# WiFiKernel.net
KiCad netlist of a schematic drawn in Altium Designer
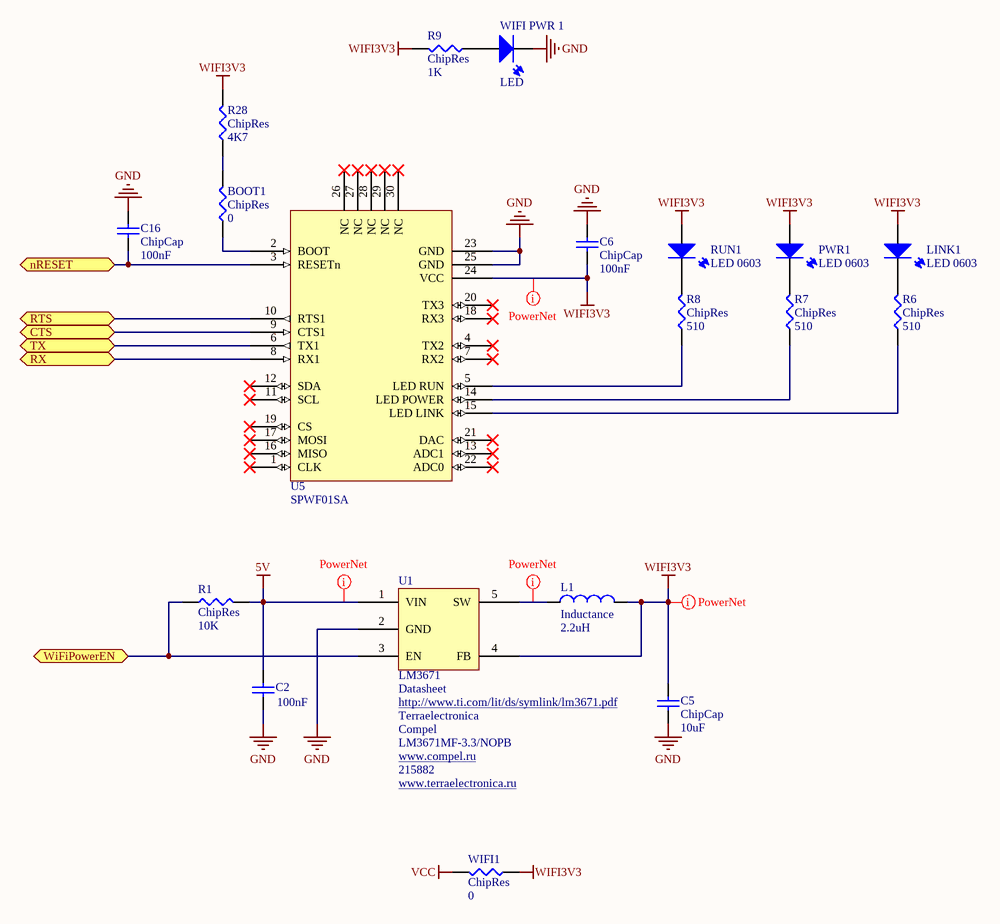
[diagram p0: WiFiKernel.SchDoc]

(export (version "E")
  (design (tool "Eeschema 10.0.6"))
  (components
    (comp (ref "BOOT1")
      (value "ChipRes")
      (footprint "RES0805")
      (description "Chip resistor")
      (fields (field (name "ALTIUM_VALUE") "0"))
      (libsource (lib "Common Devices") (part "ChipRes"))
    )
    (comp (ref "C2")
      (value "100nF")
      (footprint "CAP1210")
      (description "Capacitor")
      (fields (field (name "Comment") "ChipCap") (field (name "PUBLISHER") "Altium Limited"))
      (libsource (lib "Common Devices") (part "ChipCap"))
    )
    (comp (ref "C5")
      (value "ChipCap")
      (footprint "CAP1210")
      (description "Capacitor")
      (fields (field (name "ALTIUM_VALUE") "10uF") (field (name "PUBLISHER") "Altium Limited"))
      (libsource (lib "Common Devices") (part "ChipCap"))
    )
    (comp (ref "C6")
      (value "ChipCap")
      (footprint "CAP0805")
      (description "Capacitor")
      (fields (field (name "ALTIUM_VALUE") "100nF") (field (name "PUBLISHER") "Altium Limited"))
      (libsource (lib "Common Devices") (part "ChipCap"))
    )
    (comp (ref "C16")
      (value "ChipCap")
      (footprint "CAP0805")
      (description "Capacitor")
      (fields (field (name "ALTIUM_VALUE") "100nF") (field (name "PUBLISHER") "Altium Limited"))
      (libsource (lib "Common Devices") (part "ChipCap"))
    )
    (comp (ref "L1")
      (value "Inductance")
      (footprint "CDRH2D14")
      (fields (field (name "ALTIUM_VALUE") "2.2uH"))
      (libsource (lib "Common Devices") (part "ChipInductance"))
    )
    (comp (ref "LINK1") (value "LED 0603") (footprint "LED 0603") (libsource (lib "LEDs") (part "LED0603")))
    (comp (ref "PWR1") (value "LED 0603") (footprint "LED 0603") (libsource (lib "LEDs") (part "LED0603")))
    (comp (ref "R1")
      (value "ChipRes")
      (footprint "RES0805")
      (description "Chip resistor")
      (fields (field (name "ALTIUM_VALUE") "10K"))
      (libsource (lib "Common Devices") (part "ChipRes"))
    )
    (comp (ref "R6")
      (value "ChipRes")
      (footprint "RES0805")
      (description "Chip resistor")
      (fields (field (name "ALTIUM_VALUE") "510"))
      (libsource (lib "Common Devices") (part "ChipRes"))
    )
    (comp (ref "R7")
      (value "ChipRes")
      (footprint "RES0805")
      (description "Chip resistor")
      (fields (field (name "ALTIUM_VALUE") "510"))
      (libsource (lib "Common Devices") (part "ChipRes"))
    )
    (comp (ref "R8")
      (value "ChipRes")
      (footprint "RES0805")
      (description "Chip resistor")
      (fields (field (name "ALTIUM_VALUE") "510"))
      (libsource (lib "Common Devices") (part "ChipRes"))
    )
    (comp (ref "R9")
      (value "ChipRes")
      (footprint "RES0805")
      (description "Chip resistor")
      (fields (field (name "ALTIUM_VALUE") "1K"))
      (libsource (lib "Common Devices") (part "ChipRes"))
    )
    (comp (ref "R28")
      (value "ChipRes")
      (footprint "RES0805")
      (description "Chip resistor")
      (fields (field (name "ALTIUM_VALUE") "4K7"))
      (libsource (lib "Common Devices") (part "ChipRes"))
    )
    (comp (ref "RUN1") (value "LED 0603") (footprint "LED 0603") (libsource (lib "LEDs") (part "LED0603")))
    (comp (ref "U1")
      (value "LM3671")
      (footprint "SOT23-5")
      (description "600-mA Step-Down DC-DC Converter")
      (fields
        (field (name "COMPONENTLINK1DESCRIPTION") "Datasheet")
        (field (name "COMPONENTLINK1URL") "http://www.ti.com/lit/ds/symlink/lm3671.pdf")
        (field (name "SUPPLIER 1") "Terraelectronica")
        (field (name "SUPPLIER 2") "Compel")
        (field (name "SUPPLIER PART NUMBER 2") "LM3671MF-3.3/NOPB")
        (field (name "SUPPLIER URL 2") "www.compel.ru")
        (field (name "SUPPLIER PART NUMBER 1") "215882")
        (field (name "SUPPLIER URL 1") "www.terraelectronica.ru")
      )
      (libsource (lib "TI DC-DC Convertors") (part "LM3671MF"))
    )
    (comp (ref "U5")
      (value "SPWF01SA")
      (footprint "SPWF01SA")
      (description "Serial-to-Wi-Fi b/g/n intelligent module")
      (libsource (lib "WiFiModules") (part "SPWF01"))
    )
    (comp (ref "WIFI PWR 1") (value "LED") (footprint "PLCC-2") (libsource (lib "LEDs") (part "LED0603")))
    (comp (ref "WIFI1")
      (value "ChipRes")
      (footprint "RES0805")
      (description "Chip resistor")
      (fields (field (name "ALTIUM_VALUE") "0"))
      (libsource (lib "Common Devices") (part "ChipRes"))
    )
  )
  (nets
    (net (code "1") (name "/CTS") (class "Default")
      (node (ref "U5") (pin "9") (pinfunction "CTS1_9") (pintype "input"))
    )
    (net (code "2") (name "/RTS") (class "Default")
      (node (ref "U5") (pin "10") (pinfunction "RTS1_10") (pintype "output"))
    )
    (net (code "3") (name "/RX") (class "Default")
      (node (ref "U5") (pin "8") (pinfunction "RX1_8") (pintype "input"))
    )
    (net (code "4") (name "/TX") (class "Default")
      (node (ref "U5") (pin "6") (pinfunction "TX1_6") (pintype "output"))
    )
    (net (code "5") (name "/WiFiPowerEN") (class "Default")
      (node (ref "R1") (pin "1") (pintype "passive"))
      (node (ref "U1") (pin "3") (pinfunction "EN_3") (pintype "passive"))
    )
    (net (code "6") (name "/nRESET") (class "Default")
      (node (ref "C16") (pin "2") (pinfunction "2_2") (pintype "passive"))
      (node (ref "U5") (pin "3") (pinfunction "RESETn_3") (pintype "input"))
    )
    (net (code "7") (name "5V") (class "Default")
      (node (ref "C2") (pin "2") (pinfunction "2_2") (pintype "passive"))
      (node (ref "R1") (pin "2") (pintype "passive"))
      (node (ref "U1") (pin "1") (pinfunction "VIN_1") (pintype "passive"))
    )
    (net (code "8") (name "GND") (class "Default")
      (node (ref "C16") (pin "1") (pinfunction "1_1") (pintype "passive"))
      (node (ref "C2") (pin "1") (pinfunction "1_1") (pintype "passive"))
      (node (ref "C5") (pin "1") (pinfunction "1_1") (pintype "passive"))
      (node (ref "C6") (pin "1") (pinfunction "1_1") (pintype "passive"))
      (node (ref "U1") (pin "2") (pinfunction "GND_2") (pintype "passive"))
      (node (ref "U5") (pin "23") (pinfunction "GND_23") (pintype "passive"))
      (node (ref "U5") (pin "25") (pinfunction "GND_25") (pintype "passive"))
      (node (ref "WIFI PWR 1") (pin "1") (pinfunction "1_1") (pintype "passive"))
    )
    (net (code "9") (name "Net-(BOOT1-Pad1)") (class "Default")
      (node (ref "BOOT1") (pin "1") (pintype "passive"))
      (node (ref "R28") (pin "2") (pintype "passive"))
    )
    (net (code "10") (name "Net-(LINK1-Pad1)") (class "Default")
      (node (ref "LINK1") (pin "1") (pinfunction "1_1") (pintype "passive"))
      (node (ref "R6") (pin "1") (pintype "passive"))
    )
    (net (code "11") (name "Net-(PWR1-Pad1)") (class "Default")
      (node (ref "PWR1") (pin "1") (pinfunction "1_1") (pintype "passive"))
      (node (ref "R7") (pin "1") (pintype "passive"))
    )
    (net (code "12") (name "Net-(R8-Pad1)") (class "Default")
      (node (ref "R8") (pin "1") (pintype "passive"))
      (node (ref "RUN1") (pin "1") (pinfunction "1_1") (pintype "passive"))
    )
    (net (code "13") (name "Net-(R9-Pad1)") (class "Default")
      (node (ref "R9") (pin "1") (pintype "passive"))
      (node (ref "WIFI PWR 1") (pin "2") (pinfunction "2_2") (pintype "passive"))
    )
    (net (code "14") (name "Net-(U1-SW)") (class "Default")
      (node (ref "L1") (pin "2") (pintype "passive"))
      (node (ref "U1") (pin "5") (pinfunction "SW_5") (pintype "passive"))
    )
    (net (code "15") (name "Net-(U5-BOOT)") (class "Default")
      (node (ref "BOOT1") (pin "2") (pintype "passive"))
      (node (ref "U5") (pin "2") (pinfunction "BOOT_2") (pintype "input"))
    )
    (net (code "16") (name "Net-(U5-LED_LINK)") (class "Default")
      (node (ref "R6") (pin "2") (pintype "passive"))
      (node (ref "U5") (pin "15") (pinfunction "LED_LINK_15") (pintype "bidirectional"))
    )
    (net (code "17") (name "Net-(U5-LED_POWER)") (class "Default")
      (node (ref "R7") (pin "2") (pintype "passive"))
      (node (ref "U5") (pin "14") (pinfunction "LED_POWER_14") (pintype "bidirectional"))
    )
    (net (code "18") (name "Net-(U5-LED_RUN)") (class "Default")
      (node (ref "R8") (pin "2") (pintype "passive"))
      (node (ref "U5") (pin "5") (pinfunction "LED_RUN_5") (pintype "bidirectional"))
    )
    (net (code "19") (name "VCC") (class "Default") (node (ref "WIFI1") (pin "2") (pintype "passive")))
    (net (code "20") (name "WIFI3V3") (class "Default")
      (node (ref "C5") (pin "2") (pinfunction "2_2") (pintype "passive"))
      (node (ref "C6") (pin "2") (pinfunction "2_2") (pintype "passive"))
      (node (ref "L1") (pin "1") (pintype "passive"))
      (node (ref "LINK1") (pin "2") (pinfunction "2_2") (pintype "passive"))
      (node (ref "PWR1") (pin "2") (pinfunction "2_2") (pintype "passive"))
      (node (ref "R28") (pin "1") (pintype "passive"))
      (node (ref "R9") (pin "2") (pintype "passive"))
      (node (ref "RUN1") (pin "2") (pinfunction "2_2") (pintype "passive"))
      (node (ref "U1") (pin "4") (pinfunction "FB_4") (pintype "passive"))
      (node (ref "U5") (pin "24") (pinfunction "VCC_24") (pintype "power_in"))
      (node (ref "WIFI1") (pin "1") (pintype "passive"))
    )
    (net (code "21") (name "unconnected-(U5-ADC0-Pad22)") (class "Default")
      (node (ref "U5") (pin "22") (pinfunction "ADC0_22") (pintype "bidirectional+no_connect"))
    )
    (net (code "22") (name "unconnected-(U5-ADC1-Pad13)") (class "Default")
      (node (ref "U5") (pin "13") (pinfunction "ADC1_13") (pintype "bidirectional+no_connect"))
    )
    (net (code "23") (name "unconnected-(U5-CLK-Pad1)") (class "Default")
      (node (ref "U5") (pin "1") (pinfunction "CLK_1") (pintype "bidirectional+no_connect"))
    )
    (net (code "24") (name "unconnected-(U5-CS-Pad19)") (class "Default")
      (node (ref "U5") (pin "19") (pinfunction "CS_19") (pintype "bidirectional+no_connect"))
    )
    (net (code "25") (name "unconnected-(U5-DAC-Pad21)") (class "Default")
      (node (ref "U5") (pin "21") (pinfunction "DAC_21") (pintype "bidirectional+no_connect"))
    )
    (net (code "26") (name "unconnected-(U5-MISO-Pad16)") (class "Default")
      (node (ref "U5") (pin "16") (pinfunction "MISO_16") (pintype "bidirectional+no_connect"))
    )
    (net (code "27") (name "unconnected-(U5-MOSI-Pad17)") (class "Default")
      (node (ref "U5") (pin "17") (pinfunction "MOSI_17") (pintype "bidirectional+no_connect"))
    )
    (net (code "28") (name "unconnected-(U5-NC-Pad26)") (class "Default")
      (node (ref "U5") (pin "26") (pinfunction "NC_26") (pintype "passive+no_connect"))
    )
    (net (code "29") (name "unconnected-(U5-NC-Pad27)") (class "Default")
      (node (ref "U5") (pin "27") (pinfunction "NC_27") (pintype "passive+no_connect"))
    )
    (net (code "30") (name "unconnected-(U5-NC-Pad28)") (class "Default")
      (node (ref "U5") (pin "28") (pinfunction "NC_28") (pintype "passive+no_connect"))
    )
    (net (code "31") (name "unconnected-(U5-NC-Pad29)") (class "Default")
      (node (ref "U5") (pin "29") (pinfunction "NC_29") (pintype "passive+no_connect"))
    )
    (net (code "32") (name "unconnected-(U5-NC-Pad30)") (class "Default")
      (node (ref "U5") (pin "30") (pinfunction "NC_30") (pintype "passive+no_connect"))
    )
    (net (code "33") (name "unconnected-(U5-RX2-Pad7)") (class "Default")
      (node (ref "U5") (pin "7") (pinfunction "RX2_7") (pintype "bidirectional+no_connect"))
    )
    (net (code "34") (name "unconnected-(U5-RX3-Pad18)") (class "Default")
      (node (ref "U5") (pin "18") (pinfunction "RX3_18") (pintype "bidirectional+no_connect"))
    )
    (net (code "35") (name "unconnected-(U5-SCL-Pad11)") (class "Default")
      (node (ref "U5") (pin "11") (pinfunction "SCL_11") (pintype "bidirectional+no_connect"))
    )
    (net (code "36") (name "unconnected-(U5-SDA-Pad12)") (class "Default")
      (node (ref "U5") (pin "12") (pinfunction "SDA_12") (pintype "bidirectional+no_connect"))
    )
    (net (code "37") (name "unconnected-(U5-TX2-Pad4)") (class "Default")
      (node (ref "U5") (pin "4") (pinfunction "TX2_4") (pintype "bidirectional+no_connect"))
    )
    (net (code "38") (name "unconnected-(U5-TX3-Pad20)") (class "Default")
      (node (ref "U5") (pin "20") (pinfunction "TX3_20") (pintype "bidirectional+no_connect"))
    )
  )
)
